# Analog.net
KiCad netlist of a schematic drawn in Altium Designer
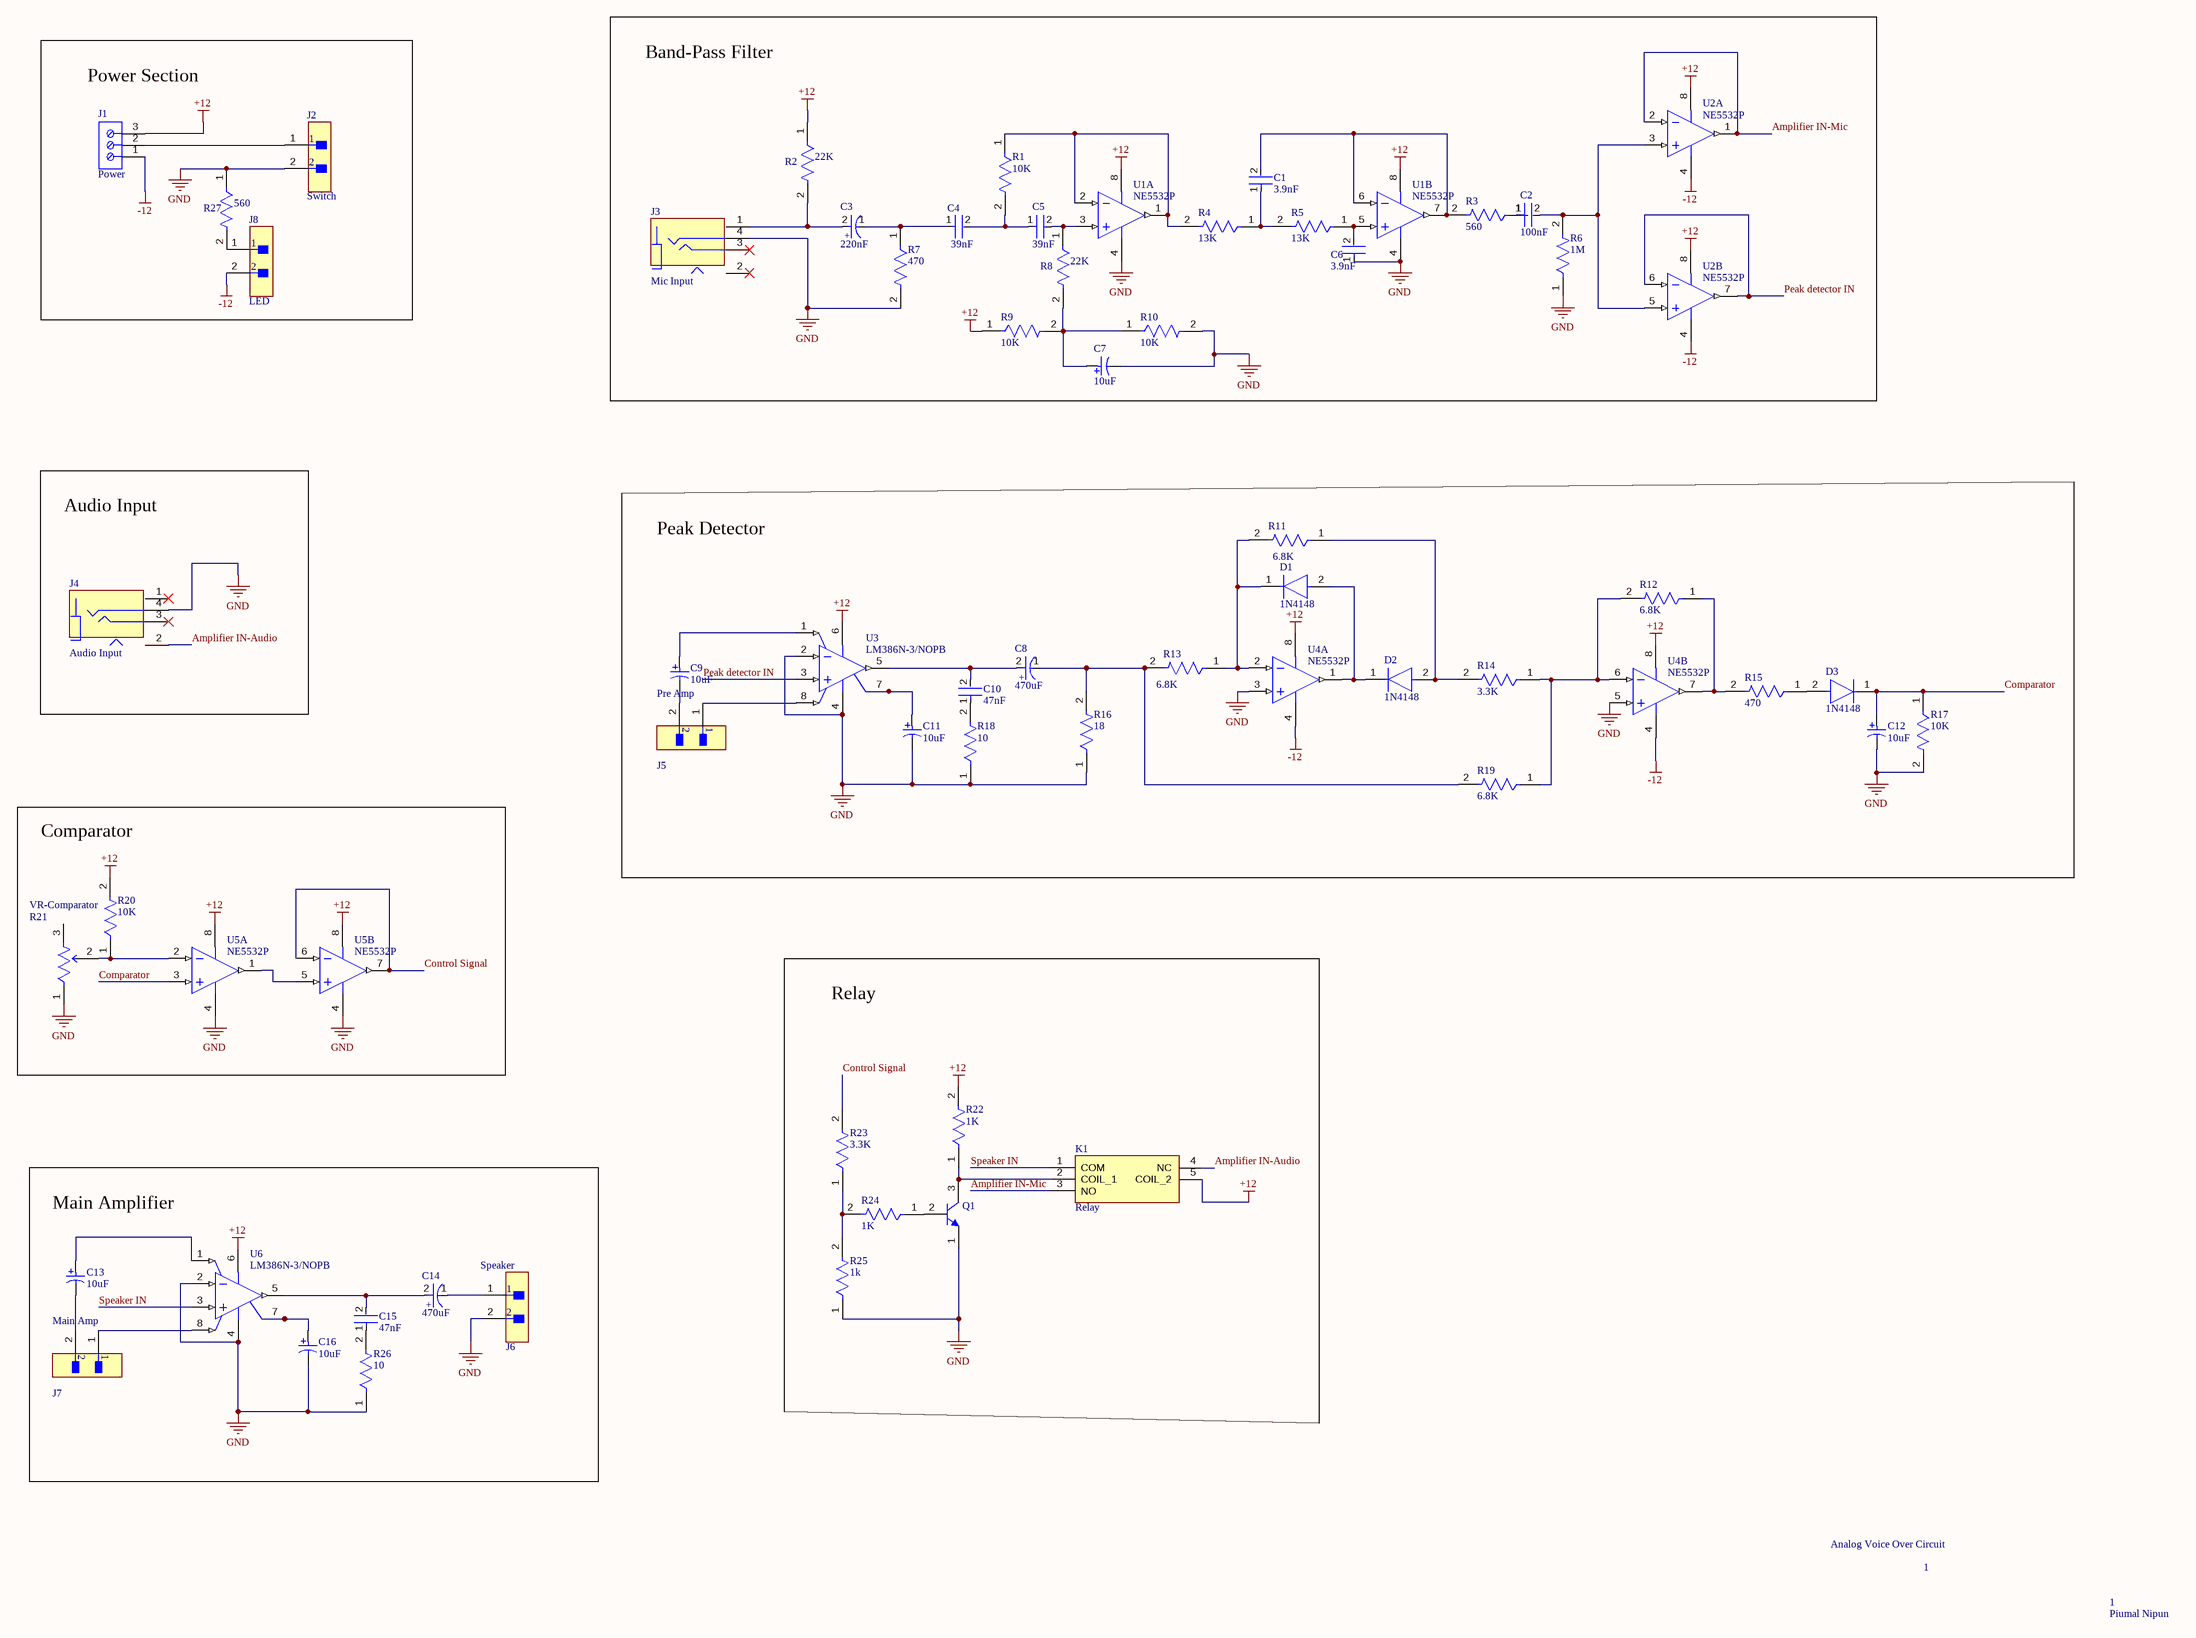
[diagram p0: Analog.SchDoc]

(export (version "E")
  (design (tool "Eeschema 10.0.6"))
  (components
    (comp (ref "C1")
      (value "3.9nF")
      (footprint "FP-RCE0DB-MFG")
      (description "Cap Ceramic 22pF 100V C0G ±5% Radial 2.5mm +125°C Ammo Pack")
      (fields (field (name "VOLTAGE") "100V") (field (name "TOLERANCE") "5%"))
      (libsource (lib "Altium Content Vault") (part "b4654b650e69147ec39a6b967a45e02"))
    )
    (comp (ref "C2")
      (value "100nF")
      (footprint "FP-RCE0DB-MFG")
      (description "Cap Ceramic 22pF 100V C0G ±5% Radial 2.5mm +125°C Ammo Pack")
      (fields (field (name "VOLTAGE") "100V") (field (name "TOLERANCE") "5%"))
      (libsource (lib "Altium Content Vault") (part "b4654b650e69147ec39a6b967a45e02"))
    )
    (comp (ref "C3")
      (value "220nF")
      (footprint "FP-RAD-TH-D_8_0_5-L_11_5-MFG")
      (description "Aluminum Electrolytic Capacitors (Radial Lead Type) 470uF ±20% 16V")
      (fields (field (name "TOLERANCE") "20%"))
      (libsource (lib "Altium Content Vault") (part "a00bbbee19879c290e62620ae7e47b1"))
    )
    (comp (ref "C4")
      (value "39nF")
      (footprint "FP-RCE0DB-MFG")
      (description "Cap Ceramic 22pF 100V C0G ±5% Radial 2.5mm +125°C Ammo Pack")
      (fields (field (name "VOLTAGE") "100V") (field (name "TOLERANCE") "5%"))
      (libsource (lib "Altium Content Vault") (part "b4654b650e69147ec39a6b967a45e02"))
    )
    (comp (ref "C5")
      (value "39nF")
      (footprint "FP-RCE0DB-MFG")
      (description "Cap Ceramic 22pF 100V C0G ±5% Radial 2.5mm +125°C Ammo Pack")
      (fields (field (name "VOLTAGE") "100V") (field (name "TOLERANCE") "5%"))
      (libsource (lib "Altium Content Vault") (part "b4654b650e69147ec39a6b967a45e02"))
    )
    (comp (ref "C6")
      (value "3.9nF")
      (footprint "FP-RCE0DB-MFG")
      (description "Cap Ceramic 22pF 100V C0G ±5% Radial 2.5mm +125°C Ammo Pack")
      (fields (field (name "VOLTAGE") "100V") (field (name "TOLERANCE") "5%"))
      (libsource (lib "Altium Content Vault") (part "b4654b650e69147ec39a6b967a45e02"))
    )
    (comp (ref "C7")
      (value "10uF")
      (footprint "CAPPR55-200-1100X500X1200")
      (description "Aluminum Electrolytic Capacitor, 10 uF, +/- 20%, 50 V, -40 to 85 degC, 2-Pin THD, RoHS, Bulk")
      (fields (field (name "MANUFACTURER") "Panasonic") (field (name "TOLERANCE") "20%"))
      (libsource (lib "Altium Content Vault") (part "CAP-P-2"))
    )
    (comp (ref "C8")
      (value "470uF")
      (footprint "FP-RAD-TH-D_8_0_5-L_11_5-MFG")
      (description "Aluminum Electrolytic Capacitors (Radial Lead Type) 470uF ±20% 16V")
      (fields (field (name "TOLERANCE") "20%"))
      (libsource (lib "Altium Content Vault") (part "a00bbbee19879c290e62620ae7e47b1"))
    )
    (comp (ref "C9")
      (value "10uF")
      (footprint "CAPPR55-200-1100X500X1200")
      (description "Aluminum Electrolytic Capacitor, 10 uF, +/- 20%, 50 V, -40 to 85 degC, 2-Pin THD, RoHS, Bulk")
      (fields (field (name "MANUFACTURER") "Panasonic") (field (name "TOLERANCE") "20%"))
      (libsource (lib "Altium Content Vault") (part "CAP-P-2"))
    )
    (comp (ref "C10")
      (value "47nF")
      (footprint "FP-RCE0DB-MFG")
      (description "Cap Ceramic 22pF 100V C0G ±5% Radial 2.5mm +125°C Ammo Pack")
      (fields (field (name "VOLTAGE") "100V") (field (name "TOLERANCE") "5%"))
      (libsource (lib "Altium Content Vault") (part "b4654b650e69147ec39a6b967a45e02"))
    )
    (comp (ref "C11")
      (value "10uF")
      (footprint "CAPPR55-200-1100X500X1200")
      (description "Aluminum Electrolytic Capacitor, 10 uF, +/- 20%, 50 V, -40 to 85 degC, 2-Pin THD, RoHS, Bulk")
      (fields (field (name "MANUFACTURER") "Panasonic") (field (name "TOLERANCE") "20%"))
      (libsource (lib "Altium Content Vault") (part "CAP-P-2"))
    )
    (comp (ref "C12")
      (value "10uF")
      (footprint "CAPPR55-200-1100X500X1200")
      (description "Aluminum Electrolytic Capacitor, 10 uF, +/- 20%, 50 V, -40 to 85 degC, 2-Pin THD, RoHS, Bulk")
      (fields (field (name "MANUFACTURER") "Panasonic") (field (name "TOLERANCE") "20%"))
      (libsource (lib "Altium Content Vault") (part "CAP-P-2"))
    )
    (comp (ref "C13")
      (value "10uF")
      (footprint "CAPPR55-200-1100X500X1200")
      (description "Aluminum Electrolytic Capacitor, 10 uF, +/- 20%, 50 V, -40 to 85 degC, 2-Pin THD, RoHS, Bulk")
      (fields (field (name "MANUFACTURER") "Panasonic") (field (name "TOLERANCE") "20%"))
      (libsource (lib "Altium Content Vault") (part "CAP-P-2"))
    )
    (comp (ref "C14")
      (value "470uF")
      (footprint "FP-RAD-TH-D_8_0_5-L_11_5-MFG")
      (description "Aluminum Electrolytic Capacitors (Radial Lead Type) 470uF ±20% 16V")
      (fields (field (name "TOLERANCE") "20%"))
      (libsource (lib "Altium Content Vault") (part "a00bbbee19879c290e62620ae7e47b1"))
    )
    (comp (ref "C15")
      (value "47nF")
      (footprint "FP-RCE0DB-MFG")
      (description "Cap Ceramic 22pF 100V C0G ±5% Radial 2.5mm +125°C Ammo Pack")
      (fields (field (name "VOLTAGE") "100V") (field (name "TOLERANCE") "5%"))
      (libsource (lib "Altium Content Vault") (part "b4654b650e69147ec39a6b967a45e02"))
    )
    (comp (ref "C16")
      (value "10uF")
      (footprint "CAPPR55-200-1100X500X1200")
      (description "Aluminum Electrolytic Capacitor, 10 uF, +/- 20%, 50 V, -40 to 85 degC, 2-Pin THD, RoHS, Bulk")
      (fields (field (name "MANUFACTURER") "Panasonic") (field (name "TOLERANCE") "20%"))
      (libsource (lib "Altium Content Vault") (part "CAP-P-2"))
    )
    (comp (ref "D1")
      (value "1N4148")
      (footprint "FP-017AG-MFG")
      (description "DIODE GEN PURP 100V 200MA DO35")
      (fields (field (name "VOLTAGE") "100V"))
      (libsource (lib "Altium Content Vault") (part "d7152d700b627762746794eb795d46e"))
    )
    (comp (ref "D2")
      (value "1N4148")
      (footprint "FP-017AG-MFG")
      (description "DIODE GEN PURP 100V 200MA DO35")
      (fields (field (name "VOLTAGE") "100V"))
      (libsource (lib "Altium Content Vault") (part "d7152d700b627762746794eb795d46e"))
    )
    (comp (ref "D3")
      (value "1N4148")
      (footprint "FP-017AG-MFG")
      (description "DIODE GEN PURP 100V 200MA DO35")
      (fields (field (name "VOLTAGE") "100V"))
      (libsource (lib "Altium Content Vault") (part "d7152d700b627762746794eb795d46e"))
    )
    (comp (ref "J1")
      (value "Power")
      (footprint "691101710003")
      (fields (field (name "VOLTAGE") "250V"))
      (libsource (lib "Altium Content Vault") (part "TBL - 1R - 03P - Screw"))
    )
    (comp (ref "J2")
      (value "Switch")
      (footprint "FP-B2B-XH-A_LF_SN-MFG")
      (description "CONN HEADER VERT 2POS 2.5MM")
      (libsource (lib "Altium Content Vault") (part "3bc925449376181038e59eaffc5286c"))
    )
    (comp (ref "J3")
      (value "Mic Input")
      (footprint "CUI_SJ2-3574A-SMT-TR")
      (description "3.5 mm, Stereo, Right Angle, Surface Mount (SMT), Audio Jack Connector")
      (fields (field (name "MP") "SJ2-3574A-SMT-TR") (field (name "MF") "CUI Devices"))
      (libsource (lib "SJ2-3574A-SMT-TR") (part "SJ2-3574A-SMT-TR"))
    )
    (comp (ref "J4")
      (value "Audio Input")
      (footprint "CUI_SJ2-3574A-SMT-TR")
      (description "3.5 mm, Stereo, Right Angle, Surface Mount (SMT), Audio Jack Connector")
      (fields (field (name "MP") "SJ2-3574A-SMT-TR") (field (name "MF") "CUI Devices"))
      (libsource (lib "SJ2-3574A-SMT-TR") (part "SJ2-3574A-SMT-TR"))
    )
    (comp (ref "J5")
      (value "Pre Amp")
      (footprint "FP-B2B-XH-A_LF_SN-MFG")
      (description "CONN HEADER VERT 2POS 2.5MM")
      (libsource (lib "") (part "3bc925449376181038e59eaffc5286c_1"))
    )
    (comp (ref "J6")
      (value "Speaker")
      (footprint "FP-B2B-XH-A_LF_SN-MFG")
      (description "CONN HEADER VERT 2POS 2.5MM")
      (libsource (lib "Altium Content Vault") (part "3bc925449376181038e59eaffc5286c"))
    )
    (comp (ref "J7")
      (value "Main Amp")
      (footprint "FP-B2B-XH-A_LF_SN-MFG")
      (description "CONN HEADER VERT 2POS 2.5MM")
      (libsource (lib "") (part "3bc925449376181038e59eaffc5286c_1"))
    )
    (comp (ref "J8")
      (value "LED")
      (footprint "FP-B2B-XH-A_LF_SN-MFG")
      (description "CONN HEADER VERT 2POS 2.5MM")
      (libsource (lib "Altium Content Vault") (part "3bc925449376181038e59eaffc5286c"))
    )
    (comp (ref "K1")
      (value "Relay")
      (footprint "SamacSys:AZ9431CH12DE")
      (description "Relay or Contactor")
      (fields (field (name "MANUFACTURER_PART_NUMBER") "AZ943-1CH-12DE"))
      (libsource (lib "*") (part "AZ943-1CH-12DE"))
    )
    (comp (ref "Q1")
      (value "~")
      (footprint "FAIR-TO-92")
      (description "NPN General-Purpose Amplifier, 40 V VCEO, 0.2 A, -55 to 150 degC, 2-Pin TO-92, RoHS, Bulk")
      (fields (field (name "MANUFACTURER") "FairchildSemiconductor"))
      (libsource (lib "Altium Content Vault") (part "NPN-E1B2C3-3"))
    )
    (comp (ref "R1")
      (value "10K")
      (footprint "FP-CF18-MFG")
      (description "RES 10K OHM 1/8W 5% CF AXIAL")
      (fields
        (field (name "MANUFACTURER PART NUMBER") "CF18JT10K0")
        (field (name "MANUFACTURER") "Stackpole Electronics")
      )
      (libsource (lib "Altium Content Vault") (part "1029c3af85768c4190bb7ad29bc67b5"))
    )
    (comp (ref "R2")
      (value "22K")
      (footprint "FP-CF18-MFG")
      (description "RES 10K OHM 1/8W 5% CF AXIAL")
      (fields
        (field (name "MANUFACTURER PART NUMBER") "CF18JT10K0")
        (field (name "MANUFACTURER") "Stackpole Electronics")
      )
      (libsource (lib "Altium Content Vault") (part "1029c3af85768c4190bb7ad29bc67b5"))
    )
    (comp (ref "R3")
      (value "560")
      (footprint "FP-CF18-MFG")
      (description "RES 10K OHM 1/8W 5% CF AXIAL")
      (fields
        (field (name "MANUFACTURER PART NUMBER") "CF18JT10K0")
        (field (name "MANUFACTURER") "Stackpole Electronics")
      )
      (libsource (lib "Altium Content Vault") (part "1029c3af85768c4190bb7ad29bc67b5"))
    )
    (comp (ref "R4")
      (value "13K")
      (footprint "FP-CF18-MFG")
      (description "RES 10K OHM 1/8W 5% CF AXIAL")
      (fields
        (field (name "MANUFACTURER PART NUMBER") "CF18JT10K0")
        (field (name "MANUFACTURER") "Stackpole Electronics")
      )
      (libsource (lib "Altium Content Vault") (part "1029c3af85768c4190bb7ad29bc67b5"))
    )
    (comp (ref "R5")
      (value "13K")
      (footprint "FP-CF18-MFG")
      (description "RES 10K OHM 1/8W 5% CF AXIAL")
      (fields
        (field (name "MANUFACTURER PART NUMBER") "CF18JT10K0")
        (field (name "MANUFACTURER") "Stackpole Electronics")
      )
      (libsource (lib "Altium Content Vault") (part "1029c3af85768c4190bb7ad29bc67b5"))
    )
    (comp (ref "R6")
      (value "1M")
      (footprint "FP-CF18-MFG")
      (description "RES 10K OHM 1/8W 5% CF AXIAL")
      (fields
        (field (name "MANUFACTURER PART NUMBER") "CF18JT10K0")
        (field (name "MANUFACTURER") "Stackpole Electronics")
      )
      (libsource (lib "Altium Content Vault") (part "1029c3af85768c4190bb7ad29bc67b5"))
    )
    (comp (ref "R7")
      (value "470")
      (footprint "FP-CF18-MFG")
      (description "RES 10K OHM 1/8W 5% CF AXIAL")
      (fields
        (field (name "MANUFACTURER PART NUMBER") "CF18JT10K0")
        (field (name "MANUFACTURER") "Stackpole Electronics")
      )
      (libsource (lib "Altium Content Vault") (part "1029c3af85768c4190bb7ad29bc67b5"))
    )
    (comp (ref "R8")
      (value "22K")
      (footprint "FP-CF18-MFG")
      (description "RES 10K OHM 1/8W 5% CF AXIAL")
      (fields
        (field (name "MANUFACTURER PART NUMBER") "CF18JT10K0")
        (field (name "MANUFACTURER") "Stackpole Electronics")
      )
      (libsource (lib "Altium Content Vault") (part "1029c3af85768c4190bb7ad29bc67b5"))
    )
    (comp (ref "R9")
      (value "10K")
      (footprint "FP-CF18-MFG")
      (description "RES 10K OHM 1/8W 5% CF AXIAL")
      (fields
        (field (name "MANUFACTURER PART NUMBER") "CF18JT10K0")
        (field (name "MANUFACTURER") "Stackpole Electronics")
      )
      (libsource (lib "Altium Content Vault") (part "1029c3af85768c4190bb7ad29bc67b5"))
    )
    (comp (ref "R10")
      (value "10K")
      (footprint "FP-CF18-MFG")
      (description "RES 10K OHM 1/8W 5% CF AXIAL")
      (fields
        (field (name "MANUFACTURER PART NUMBER") "CF18JT10K0")
        (field (name "MANUFACTURER") "Stackpole Electronics")
      )
      (libsource (lib "Altium Content Vault") (part "1029c3af85768c4190bb7ad29bc67b5"))
    )
    (comp (ref "R11")
      (value "6.8K")
      (footprint "FP-CF18-MFG")
      (description "RES 10K OHM 1/8W 5% CF AXIAL")
      (fields
        (field (name "MANUFACTURER PART NUMBER") "CF18JT10K0")
        (field (name "MANUFACTURER") "Stackpole Electronics")
      )
      (libsource (lib "Altium Content Vault") (part "1029c3af85768c4190bb7ad29bc67b5"))
    )
    (comp (ref "R12")
      (value "6.8K")
      (footprint "FP-CF18-MFG")
      (description "RES 10K OHM 1/8W 5% CF AXIAL")
      (fields
        (field (name "MANUFACTURER PART NUMBER") "CF18JT10K0")
        (field (name "MANUFACTURER") "Stackpole Electronics")
      )
      (libsource (lib "Altium Content Vault") (part "1029c3af85768c4190bb7ad29bc67b5"))
    )
    (comp (ref "R13")
      (value "6.8K")
      (footprint "FP-CF18-MFG")
      (description "RES 10K OHM 1/8W 5% CF AXIAL")
      (fields
        (field (name "MANUFACTURER PART NUMBER") "CF18JT10K0")
        (field (name "MANUFACTURER") "Stackpole Electronics")
      )
      (libsource (lib "Altium Content Vault") (part "1029c3af85768c4190bb7ad29bc67b5"))
    )
    (comp (ref "R14")
      (value "3.3K")
      (footprint "FP-CF18-MFG")
      (description "RES 10K OHM 1/8W 5% CF AXIAL")
      (fields
        (field (name "MANUFACTURER PART NUMBER") "CF18JT10K0")
        (field (name "MANUFACTURER") "Stackpole Electronics")
      )
      (libsource (lib "Altium Content Vault") (part "1029c3af85768c4190bb7ad29bc67b5"))
    )
    (comp (ref "R15")
      (value "470")
      (footprint "FP-CF18-MFG")
      (description "RES 10K OHM 1/8W 5% CF AXIAL")
      (fields
        (field (name "MANUFACTURER PART NUMBER") "CF18JT10K0")
        (field (name "MANUFACTURER") "Stackpole Electronics")
      )
      (libsource (lib "Altium Content Vault") (part "1029c3af85768c4190bb7ad29bc67b5"))
    )
    (comp (ref "R16")
      (value "18")
      (footprint "FP-CF18-MFG")
      (description "RES 10K OHM 1/8W 5% CF AXIAL")
      (fields
        (field (name "MANUFACTURER PART NUMBER") "CF18JT10K0")
        (field (name "MANUFACTURER") "Stackpole Electronics")
      )
      (libsource (lib "Altium Content Vault") (part "1029c3af85768c4190bb7ad29bc67b5"))
    )
    (comp (ref "R17")
      (value "10K")
      (footprint "FP-CF18-MFG")
      (description "RES 10K OHM 1/8W 5% CF AXIAL")
      (fields
        (field (name "MANUFACTURER PART NUMBER") "CF18JT10K0")
        (field (name "MANUFACTURER") "Stackpole Electronics")
      )
      (libsource (lib "Altium Content Vault") (part "1029c3af85768c4190bb7ad29bc67b5"))
    )
    (comp (ref "R18")
      (value "10")
      (footprint "FP-CF18-MFG")
      (description "RES 10K OHM 1/8W 5% CF AXIAL")
      (fields
        (field (name "MANUFACTURER PART NUMBER") "CF18JT10K0")
        (field (name "MANUFACTURER") "Stackpole Electronics")
      )
      (libsource (lib "Altium Content Vault") (part "1029c3af85768c4190bb7ad29bc67b5"))
    )
    (comp (ref "R19")
      (value "6.8K")
      (footprint "FP-CF18-MFG")
      (description "RES 10K OHM 1/8W 5% CF AXIAL")
      (fields
        (field (name "MANUFACTURER PART NUMBER") "CF18JT10K0")
        (field (name "MANUFACTURER") "Stackpole Electronics")
      )
      (libsource (lib "Altium Content Vault") (part "1029c3af85768c4190bb7ad29bc67b5"))
    )
    (comp (ref "R20")
      (value "10K")
      (footprint "FP-CF18-MFG")
      (description "RES 10K OHM 1/8W 5% CF AXIAL")
      (fields
        (field (name "MANUFACTURER PART NUMBER") "CF18JT10K0")
        (field (name "MANUFACTURER") "Stackpole Electronics")
      )
      (libsource (lib "Altium Content Vault") (part "1029c3af85768c4190bb7ad29bc67b5"))
    )
    (comp (ref "R21")
      (value "VR-Comparator")
      (footprint "FP-3296W-MFG")
      (description "TRIMMER 10K OHM 0.5W PC PIN TOP")
      (fields (field (name "TOLERANCE") "10%"))
      (libsource (lib "Altium Content Vault") (part "2dcfd2547301a7d3209a5e99acfd772"))
    )
    (comp (ref "R22")
      (value "1K")
      (footprint "FP-CF18-MFG")
      (description "RES 10K OHM 1/8W 5% CF AXIAL")
      (fields
        (field (name "MANUFACTURER PART NUMBER") "CF18JT10K0")
        (field (name "MANUFACTURER") "Stackpole Electronics")
      )
      (libsource (lib "Altium Content Vault") (part "1029c3af85768c4190bb7ad29bc67b5"))
    )
    (comp (ref "R23")
      (value "3.3K")
      (footprint "FP-CF18-MFG")
      (description "RES 10K OHM 1/8W 5% CF AXIAL")
      (fields
        (field (name "MANUFACTURER PART NUMBER") "CF18JT10K0")
        (field (name "MANUFACTURER") "Stackpole Electronics")
      )
      (libsource (lib "Altium Content Vault") (part "1029c3af85768c4190bb7ad29bc67b5"))
    )
    (comp (ref "R24")
      (value "1K")
      (footprint "FP-CF18-MFG")
      (description "RES 10K OHM 1/8W 5% CF AXIAL")
      (fields
        (field (name "MANUFACTURER PART NUMBER") "CF18JT10K0")
        (field (name "MANUFACTURER") "Stackpole Electronics")
      )
      (libsource (lib "Altium Content Vault") (part "1029c3af85768c4190bb7ad29bc67b5"))
    )
    (comp (ref "R25")
      (value "1k")
      (footprint "FP-CF18-MFG")
      (description "RES 10K OHM 1/8W 5% CF AXIAL")
      (fields
        (field (name "MANUFACTURER PART NUMBER") "CF18JT10K0")
        (field (name "MANUFACTURER") "Stackpole Electronics")
      )
      (libsource (lib "Altium Content Vault") (part "1029c3af85768c4190bb7ad29bc67b5"))
    )
    (comp (ref "R26")
      (value "10")
      (footprint "FP-CF18-MFG")
      (description "RES 10K OHM 1/8W 5% CF AXIAL")
      (fields
        (field (name "MANUFACTURER PART NUMBER") "CF18JT10K0")
        (field (name "MANUFACTURER") "Stackpole Electronics")
      )
      (libsource (lib "Altium Content Vault") (part "1029c3af85768c4190bb7ad29bc67b5"))
    )
    (comp (ref "R27")
      (value "560")
      (footprint "FP-CF18-MFG")
      (description "RES 10K OHM 1/8W 5% CF AXIAL")
      (fields
        (field (name "MANUFACTURER PART NUMBER") "CF18JT10K0")
        (field (name "MANUFACTURER") "Stackpole Electronics")
      )
      (libsource (lib "Altium Content Vault") (part "1029c3af85768c4190bb7ad29bc67b5"))
    )
    (comp (ref "U1")
      (value "NE5532P")
      (footprint "P0008A")
      (fields (field (name "MANUFACTURER") "Texas Instruments"))
      (libsource (lib "Altium Content Vault") (part "TI-AMP-D6-2-8_D"))
    )
    (comp (ref "U2")
      (value "NE5532P")
      (footprint "P0008A")
      (fields (field (name "MANUFACTURER") "Texas Instruments"))
      (libsource (lib "Altium Content Vault") (part "TI-AMP-D6-2-8_D"))
    )
    (comp (ref "U3")
      (value "LM386N-3/NOPB")
      (footprint "TI-P8")
      (description "Low Voltage Audio Power Amplifier, 0 to 70 degC, 8-pin DIP (P8), Green (RoHS & no Sb/Br)")
      (fields (field (name "MANUFACTURER") "Texas Instruments"))
      (libsource (lib "Altium Content Vault") (part "TI-LM386undefined"))
    )
    (comp (ref "U4")
      (value "NE5532P")
      (footprint "P0008A")
      (fields (field (name "MANUFACTURER") "Texas Instruments"))
      (libsource (lib "Altium Content Vault") (part "TI-AMP-D6-2-8_D"))
    )
    (comp (ref "U5")
      (value "NE5532P")
      (footprint "P0008A")
      (fields (field (name "MANUFACTURER") "Texas Instruments"))
      (libsource (lib "Altium Content Vault") (part "TI-AMP-D6-2-8_D"))
    )
    (comp (ref "U6")
      (value "LM386N-3/NOPB")
      (footprint "TI-P8")
      (description "Low Voltage Audio Power Amplifier, 0 to 70 degC, 8-pin DIP (P8), Green (RoHS & no Sb/Br)")
      (fields (field (name "MANUFACTURER") "Texas Instruments"))
      (libsource (lib "Altium Content Vault") (part "TI-LM386undefined"))
    )
  )
  (nets
    (net (code "1") (name "+12") (class "Default")
      (node (ref "J1") (pin "3") (pinfunction "3_3") (pintype "passive"))
      (node (ref "K1") (pin "5") (pinfunction "COIL_2_5") (pintype "passive"))
      (node (ref "R2") (pin "1") (pinfunction "1_1") (pintype "passive"))
      (node (ref "R20") (pin "2") (pinfunction "2_2") (pintype "passive"))
      (node (ref "R22") (pin "2") (pinfunction "2_2") (pintype "passive"))
      (node (ref "R9") (pin "1") (pinfunction "1_1") (pintype "passive"))
      (node (ref "U1") (pin "8") (pinfunction "VCC+_8") (pintype "power_in"))
      (node (ref "U2") (pin "8") (pinfunction "VCC+_8") (pintype "power_in"))
      (node (ref "U3") (pin "6") (pinfunction "VS_6") (pintype "power_in"))
      (node (ref "U4") (pin "8") (pinfunction "VCC+_8") (pintype "power_in"))
      (node (ref "U5") (pin "8") (pinfunction "VCC+_8") (pintype "power_in"))
      (node (ref "U6") (pin "6") (pinfunction "VS_6") (pintype "power_in"))
    )
    (net (code "2") (name "-12") (class "Default")
      (node (ref "J1") (pin "1") (pinfunction "1_1") (pintype "passive"))
      (node (ref "J8") (pin "2") (pinfunction "2_2") (pintype "passive"))
      (node (ref "U2") (pin "4") (pinfunction "VCC-_4") (pintype "power_in"))
      (node (ref "U4") (pin "4") (pinfunction "VCC-_4") (pintype "power_in"))
    )
    (net (code "3") (name "/Amplifier IN-Audio") (class "Default")
      (node (ref "J4") (pin "2") (pinfunction "2_2") (pintype "passive"))
      (node (ref "K1") (pin "4") (pinfunction "NC_4") (pintype "passive"))
    )
    (net (code "4") (name "/Amplifier IN-Mic") (class "Default")
      (node (ref "K1") (pin "3") (pinfunction "NO_3") (pintype "passive"))
      (node (ref "U2") (pin "1") (pinfunction "OUT1_1") (pintype "output"))
      (node (ref "U2") (pin "2") (pinfunction "IN1-_2") (pintype "input"))
    )
    (net (code "5") (name "/Comparator") (class "Default")
      (node (ref "C12") (pin "1") (pinfunction "1_1") (pintype "passive"))
      (node (ref "D3") (pin "1") (pinfunction "C_1") (pintype "passive"))
      (node (ref "R17") (pin "1") (pinfunction "1_1") (pintype "passive"))
      (node (ref "U5") (pin "3") (pinfunction "IN1+_3") (pintype "input"))
    )
    (net (code "6") (name "/Control Signal") (class "Default")
      (node (ref "R23") (pin "2") (pinfunction "2_2") (pintype "passive"))
      (node (ref "U5") (pin "6") (pinfunction "IN2-_6") (pintype "input"))
      (node (ref "U5") (pin "7") (pinfunction "OUT2_7") (pintype "output"))
    )
    (net (code "7") (name "/Peak detector IN") (class "Default")
      (node (ref "U2") (pin "6") (pinfunction "IN2-_6") (pintype "input"))
      (node (ref "U2") (pin "7") (pinfunction "OUT2_7") (pintype "output"))
      (node (ref "U3") (pin "3") (pinfunction "IN+_3") (pintype "input"))
    )
    (net (code "8") (name "/Speaker IN") (class "Default")
      (node (ref "K1") (pin "1") (pinfunction "COM_1") (pintype "passive"))
      (node (ref "U6") (pin "3") (pinfunction "IN+_3") (pintype "input"))
    )
    (net (code "9") (name "GND") (class "Default")
      (node (ref "C11") (pin "2") (pinfunction "2_2") (pintype "passive"))
      (node (ref "C12") (pin "2") (pinfunction "2_2") (pintype "passive"))
      (node (ref "C16") (pin "2") (pinfunction "2_2") (pintype "passive"))
      (node (ref "C6") (pin "1") (pinfunction "1_1") (pintype "passive"))
      (node (ref "C7") (pin "2") (pinfunction "2_2") (pintype "passive"))
      (node (ref "J2") (pin "2") (pinfunction "2_2") (pintype "passive"))
      (node (ref "J3") (pin "4") (pinfunction "4_4") (pintype "passive"))
      (node (ref "J4") (pin "4") (pinfunction "4_4") (pintype "passive"))
      (node (ref "J6") (pin "2") (pinfunction "2_2") (pintype "passive"))
      (node (ref "Q1") (pin "1") (pinfunction "E_1") (pintype "passive"))
      (node (ref "R10") (pin "2") (pinfunction "2_2") (pintype "passive"))
      (node (ref "R16") (pin "1") (pinfunction "1_1") (pintype "passive"))
      (node (ref "R17") (pin "2") (pinfunction "2_2") (pintype "passive"))
      (node (ref "R18") (pin "1") (pinfunction "1_1") (pintype "passive"))
      (node (ref "R21") (pin "1") (pinfunction "CCW_1") (pintype "passive"))
      (node (ref "R25") (pin "1") (pinfunction "1_1") (pintype "passive"))
      (node (ref "R26") (pin "1") (pinfunction "1_1") (pintype "passive"))
      (node (ref "R27") (pin "1") (pinfunction "1_1") (pintype "passive"))
      (node (ref "R6") (pin "1") (pinfunction "1_1") (pintype "passive"))
      (node (ref "R7") (pin "2") (pinfunction "2_2") (pintype "passive"))
      (node (ref "U1") (pin "4") (pinfunction "VCC-_4") (pintype "power_in"))
      (node (ref "U3") (pin "2") (pinfunction "IN-_2") (pintype "input"))
      (node (ref "U3") (pin "4") (pinfunction "GND_4") (pintype "power_in"))
      (node (ref "U4") (pin "3") (pinfunction "IN1+_3") (pintype "input"))
      (node (ref "U4") (pin "5") (pinfunction "IN2+_5") (pintype "input"))
      (node (ref "U5") (pin "4") (pinfunction "VCC-_4") (pintype "power_in"))
      (node (ref "U6") (pin "2") (pinfunction "IN-_2") (pintype "input"))
      (node (ref "U6") (pin "4") (pinfunction "GND_4") (pintype "power_in"))
    )
    (net (code "10") (name "Net-(C1-Pad1)") (class "Default")
      (node (ref "C1") (pin "1") (pinfunction "1_1") (pintype "passive"))
      (node (ref "R4") (pin "1") (pinfunction "1_1") (pintype "passive"))
      (node (ref "R5") (pin "2") (pinfunction "2_2") (pintype "passive"))
    )
    (net (code "11") (name "Net-(C2-Pad1)") (class "Default")
      (node (ref "C2") (pin "1") (pinfunction "1_1") (pintype "passive"))
      (node (ref "R3") (pin "1") (pinfunction "1_1") (pintype "passive"))
    )
    (net (code "12") (name "Net-(C3-A)") (class "Default")
      (node (ref "C3") (pin "2") (pinfunction "A_2") (pintype "passive"))
      (node (ref "J3") (pin "1") (pinfunction "1_1") (pintype "passive"))
      (node (ref "R2") (pin "2") (pinfunction "2_2") (pintype "passive"))
    )
    (net (code "13") (name "Net-(C3-C)") (class "Default")
      (node (ref "C3") (pin "1") (pinfunction "C_1") (pintype "passive"))
      (node (ref "C4") (pin "1") (pinfunction "1_1") (pintype "passive"))
      (node (ref "R7") (pin "1") (pinfunction "1_1") (pintype "passive"))
    )
    (net (code "14") (name "Net-(C4-Pad2)") (class "Default")
      (node (ref "C4") (pin "2") (pinfunction "2_2") (pintype "passive"))
      (node (ref "C5") (pin "1") (pinfunction "1_1") (pintype "passive"))
      (node (ref "R1") (pin "2") (pinfunction "2_2") (pintype "passive"))
    )
    (net (code "15") (name "Net-(C7-Pad1)") (class "Default")
      (node (ref "C7") (pin "1") (pinfunction "1_1") (pintype "passive"))
      (node (ref "R10") (pin "1") (pinfunction "1_1") (pintype "passive"))
      (node (ref "R8") (pin "2") (pinfunction "2_2") (pintype "passive"))
      (node (ref "R9") (pin "2") (pinfunction "2_2") (pintype "passive"))
    )
    (net (code "16") (name "Net-(C8-A)") (class "Default")
      (node (ref "C10") (pin "2") (pinfunction "2_2") (pintype "passive"))
      (node (ref "C8") (pin "2") (pinfunction "A_2") (pintype "passive"))
      (node (ref "U3") (pin "5") (pinfunction "VOUT_5") (pintype "output"))
    )
    (net (code "17") (name "Net-(C8-C)") (class "Default")
      (node (ref "C8") (pin "1") (pinfunction "C_1") (pintype "passive"))
      (node (ref "R13") (pin "2") (pinfunction "2_2") (pintype "passive"))
      (node (ref "R16") (pin "2") (pinfunction "2_2") (pintype "passive"))
      (node (ref "R19") (pin "2") (pinfunction "2_2") (pintype "passive"))
    )
    (net (code "18") (name "Net-(C9-Pad1)") (class "Default")
      (node (ref "C9") (pin "1") (pinfunction "1_1") (pintype "passive"))
      (node (ref "U3") (pin "1") (pinfunction "GAIN_1") (pintype "input"))
    )
    (net (code "19") (name "Net-(C9-Pad2)") (class "Default")
      (node (ref "C9") (pin "2") (pinfunction "2_2") (pintype "passive"))
      (node (ref "J5") (pin "2") (pinfunction "2_2") (pintype "passive"))
    )
    (net (code "20") (name "Net-(C10-Pad1)") (class "Default")
      (node (ref "C10") (pin "1") (pinfunction "1_1") (pintype "passive"))
      (node (ref "R18") (pin "2") (pinfunction "2_2") (pintype "passive"))
    )
    (net (code "21") (name "Net-(C13-Pad1)") (class "Default")
      (node (ref "C13") (pin "1") (pinfunction "1_1") (pintype "passive"))
      (node (ref "U6") (pin "1") (pinfunction "GAIN_1") (pintype "input"))
    )
    (net (code "22") (name "Net-(C13-Pad2)") (class "Default")
      (node (ref "C13") (pin "2") (pinfunction "2_2") (pintype "passive"))
      (node (ref "J7") (pin "2") (pinfunction "2_2") (pintype "passive"))
    )
    (net (code "23") (name "Net-(C14-A)") (class "Default")
      (node (ref "C14") (pin "2") (pinfunction "A_2") (pintype "passive"))
      (node (ref "C15") (pin "2") (pinfunction "2_2") (pintype "passive"))
      (node (ref "U6") (pin "5") (pinfunction "VOUT_5") (pintype "output"))
    )
    (net (code "24") (name "Net-(C14-C)") (class "Default")
      (node (ref "C14") (pin "1") (pinfunction "C_1") (pintype "passive"))
      (node (ref "J6") (pin "1") (pinfunction "1_1") (pintype "passive"))
    )
    (net (code "25") (name "Net-(C15-Pad1)") (class "Default")
      (node (ref "C15") (pin "1") (pinfunction "1_1") (pintype "passive"))
      (node (ref "R26") (pin "2") (pinfunction "2_2") (pintype "passive"))
    )
    (net (code "26") (name "Net-(D1-A)") (class "Default")
      (node (ref "D1") (pin "2") (pinfunction "A_2") (pintype "passive"))
      (node (ref "D2") (pin "1") (pinfunction "C_1") (pintype "passive"))
      (node (ref "U4") (pin "1") (pinfunction "OUT1_1") (pintype "output"))
    )
    (net (code "27") (name "Net-(D1-C)") (class "Default")
      (node (ref "D1") (pin "1") (pinfunction "C_1") (pintype "passive"))
      (node (ref "R11") (pin "2") (pinfunction "2_2") (pintype "passive"))
      (node (ref "R13") (pin "1") (pinfunction "1_1") (pintype "passive"))
      (node (ref "U4") (pin "2") (pinfunction "IN1-_2") (pintype "input"))
    )
    (net (code "28") (name "Net-(D2-A)") (class "Default")
      (node (ref "D2") (pin "2") (pinfunction "A_2") (pintype "passive"))
      (node (ref "R11") (pin "1") (pinfunction "1_1") (pintype "passive"))
      (node (ref "R14") (pin "2") (pinfunction "2_2") (pintype "passive"))
    )
    (net (code "29") (name "Net-(D3-A)") (class "Default")
      (node (ref "D3") (pin "2") (pinfunction "A_2") (pintype "passive"))
      (node (ref "R15") (pin "1") (pinfunction "1_1") (pintype "passive"))
    )
    (net (code "30") (name "Net-(J1-Pad2)") (class "Default")
      (node (ref "J1") (pin "2") (pinfunction "2_2") (pintype "passive"))
      (node (ref "J2") (pin "1") (pinfunction "1_1") (pintype "passive"))
    )
    (net (code "31") (name "Net-(J5-Pad1)") (class "Default")
      (node (ref "J5") (pin "1") (pinfunction "1_1") (pintype "passive"))
      (node (ref "U3") (pin "8") (pinfunction "GAIN_8") (pintype "input"))
    )
    (net (code "32") (name "Net-(J7-Pad1)") (class "Default")
      (node (ref "J7") (pin "1") (pinfunction "1_1") (pintype "passive"))
      (node (ref "U6") (pin "8") (pinfunction "GAIN_8") (pintype "input"))
    )
    (net (code "33") (name "Net-(J8-Pad1)") (class "Default")
      (node (ref "J8") (pin "1") (pinfunction "1_1") (pintype "passive"))
      (node (ref "R27") (pin "2") (pinfunction "2_2") (pintype "passive"))
    )
    (net (code "34") (name "Net-(K1-COIL_1)") (class "Default")
      (node (ref "K1") (pin "2") (pinfunction "COIL_1_2") (pintype "passive"))
      (node (ref "Q1") (pin "3") (pinfunction "C_3") (pintype "passive"))
      (node (ref "R22") (pin "1") (pinfunction "1_1") (pintype "passive"))
    )
    (net (code "35") (name "Net-(Q1-B)") (class "Default")
      (node (ref "Q1") (pin "2") (pinfunction "B_2") (pintype "passive"))
      (node (ref "R24") (pin "1") (pinfunction "1_1") (pintype "passive"))
    )
    (net (code "36") (name "Net-(R21-WIPER)") (class "Default")
      (node (ref "R20") (pin "1") (pinfunction "1_1") (pintype "passive"))
      (node (ref "R21") (pin "2") (pinfunction "WIPER_2") (pintype "passive"))
      (node (ref "U5") (pin "2") (pinfunction "IN1-_2") (pintype "input"))
    )
    (net (code "37") (name "Net-(R23-Pad1)") (class "Default")
      (node (ref "R23") (pin "1") (pinfunction "1_1") (pintype "passive"))
      (node (ref "R24") (pin "2") (pinfunction "2_2") (pintype "passive"))
      (node (ref "R25") (pin "2") (pinfunction "2_2") (pintype "passive"))
    )
    (net (code "38") (name "Net-(U1A-IN1+)") (class "Default")
      (node (ref "C5") (pin "2") (pinfunction "2_2") (pintype "passive"))
      (node (ref "R8") (pin "1") (pinfunction "1_1") (pintype "passive"))
      (node (ref "U1") (pin "3") (pinfunction "IN1+_3") (pintype "input"))
    )
    (net (code "39") (name "Net-(U1A-IN1-)") (class "Default")
      (node (ref "R1") (pin "1") (pinfunction "1_1") (pintype "passive"))
      (node (ref "R4") (pin "2") (pinfunction "2_2") (pintype "passive"))
      (node (ref "U1") (pin "1") (pinfunction "OUT1_1") (pintype "output"))
      (node (ref "U1") (pin "2") (pinfunction "IN1-_2") (pintype "input"))
    )
    (net (code "40") (name "Net-(U1B-IN2+)") (class "Default")
      (node (ref "C6") (pin "2") (pinfunction "2_2") (pintype "passive"))
      (node (ref "R5") (pin "1") (pinfunction "1_1") (pintype "passive"))
      (node (ref "U1") (pin "5") (pinfunction "IN2+_5") (pintype "input"))
    )
    (net (code "41") (name "Net-(U1B-IN2-)") (class "Default")
      (node (ref "C1") (pin "2") (pinfunction "2_2") (pintype "passive"))
      (node (ref "R3") (pin "2") (pinfunction "2_2") (pintype "passive"))
      (node (ref "U1") (pin "6") (pinfunction "IN2-_6") (pintype "input"))
      (node (ref "U1") (pin "7") (pinfunction "OUT2_7") (pintype "output"))
    )
    (net (code "42") (name "Net-(U2A-IN1+)") (class "Default")
      (node (ref "C2") (pin "2") (pinfunction "2_2") (pintype "passive"))
      (node (ref "R6") (pin "2") (pinfunction "2_2") (pintype "passive"))
      (node (ref "U2") (pin "3") (pinfunction "IN1+_3") (pintype "input"))
      (node (ref "U2") (pin "5") (pinfunction "IN2+_5") (pintype "input"))
    )
    (net (code "43") (name "Net-(U3-BYPASS)") (class "Default")
      (node (ref "C11") (pin "1") (pinfunction "1_1") (pintype "passive"))
      (node (ref "U3") (pin "7") (pinfunction "BYPASS_7") (pintype "passive"))
    )
    (net (code "44") (name "Net-(U4B-IN2-)") (class "Default")
      (node (ref "R12") (pin "2") (pinfunction "2_2") (pintype "passive"))
      (node (ref "R14") (pin "1") (pinfunction "1_1") (pintype "passive"))
      (node (ref "R19") (pin "1") (pinfunction "1_1") (pintype "passive"))
      (node (ref "U4") (pin "6") (pinfunction "IN2-_6") (pintype "input"))
    )
    (net (code "45") (name "Net-(U4B-OUT2)") (class "Default")
      (node (ref "R12") (pin "1") (pinfunction "1_1") (pintype "passive"))
      (node (ref "R15") (pin "2") (pinfunction "2_2") (pintype "passive"))
      (node (ref "U4") (pin "7") (pinfunction "OUT2_7") (pintype "output"))
    )
    (net (code "46") (name "Net-(U5A-OUT1)") (class "Default")
      (node (ref "U5") (pin "1") (pinfunction "OUT1_1") (pintype "output"))
      (node (ref "U5") (pin "5") (pinfunction "IN2+_5") (pintype "input"))
    )
    (net (code "47") (name "Net-(U6-BYPASS)") (class "Default")
      (node (ref "C16") (pin "1") (pinfunction "1_1") (pintype "passive"))
      (node (ref "U6") (pin "7") (pinfunction "BYPASS_7") (pintype "passive"))
    )
    (net (code "48") (name "unconnected-(J3-Pad2)") (class "Default")
      (node (ref "J3") (pin "2") (pinfunction "2_2") (pintype "passive+no_connect"))
    )
    (net (code "49") (name "unconnected-(J3-Pad3)") (class "Default")
      (node (ref "J3") (pin "3") (pinfunction "3_3") (pintype "passive+no_connect"))
    )
    (net (code "50") (name "unconnected-(J4-Pad1)") (class "Default")
      (node (ref "J4") (pin "1") (pinfunction "1_1") (pintype "passive+no_connect"))
    )
    (net (code "51") (name "unconnected-(J4-Pad3)") (class "Default")
      (node (ref "J4") (pin "3") (pinfunction "3_3") (pintype "passive+no_connect"))
    )
    (net (code "52") (name "unconnected-(R21-CW-Pad3)") (class "Default")
      (node (ref "R21") (pin "3") (pinfunction "CW_3") (pintype "passive"))
    )
  )
)
